# single84.net
KiCad netlist of a schematic drawn in EAGLE
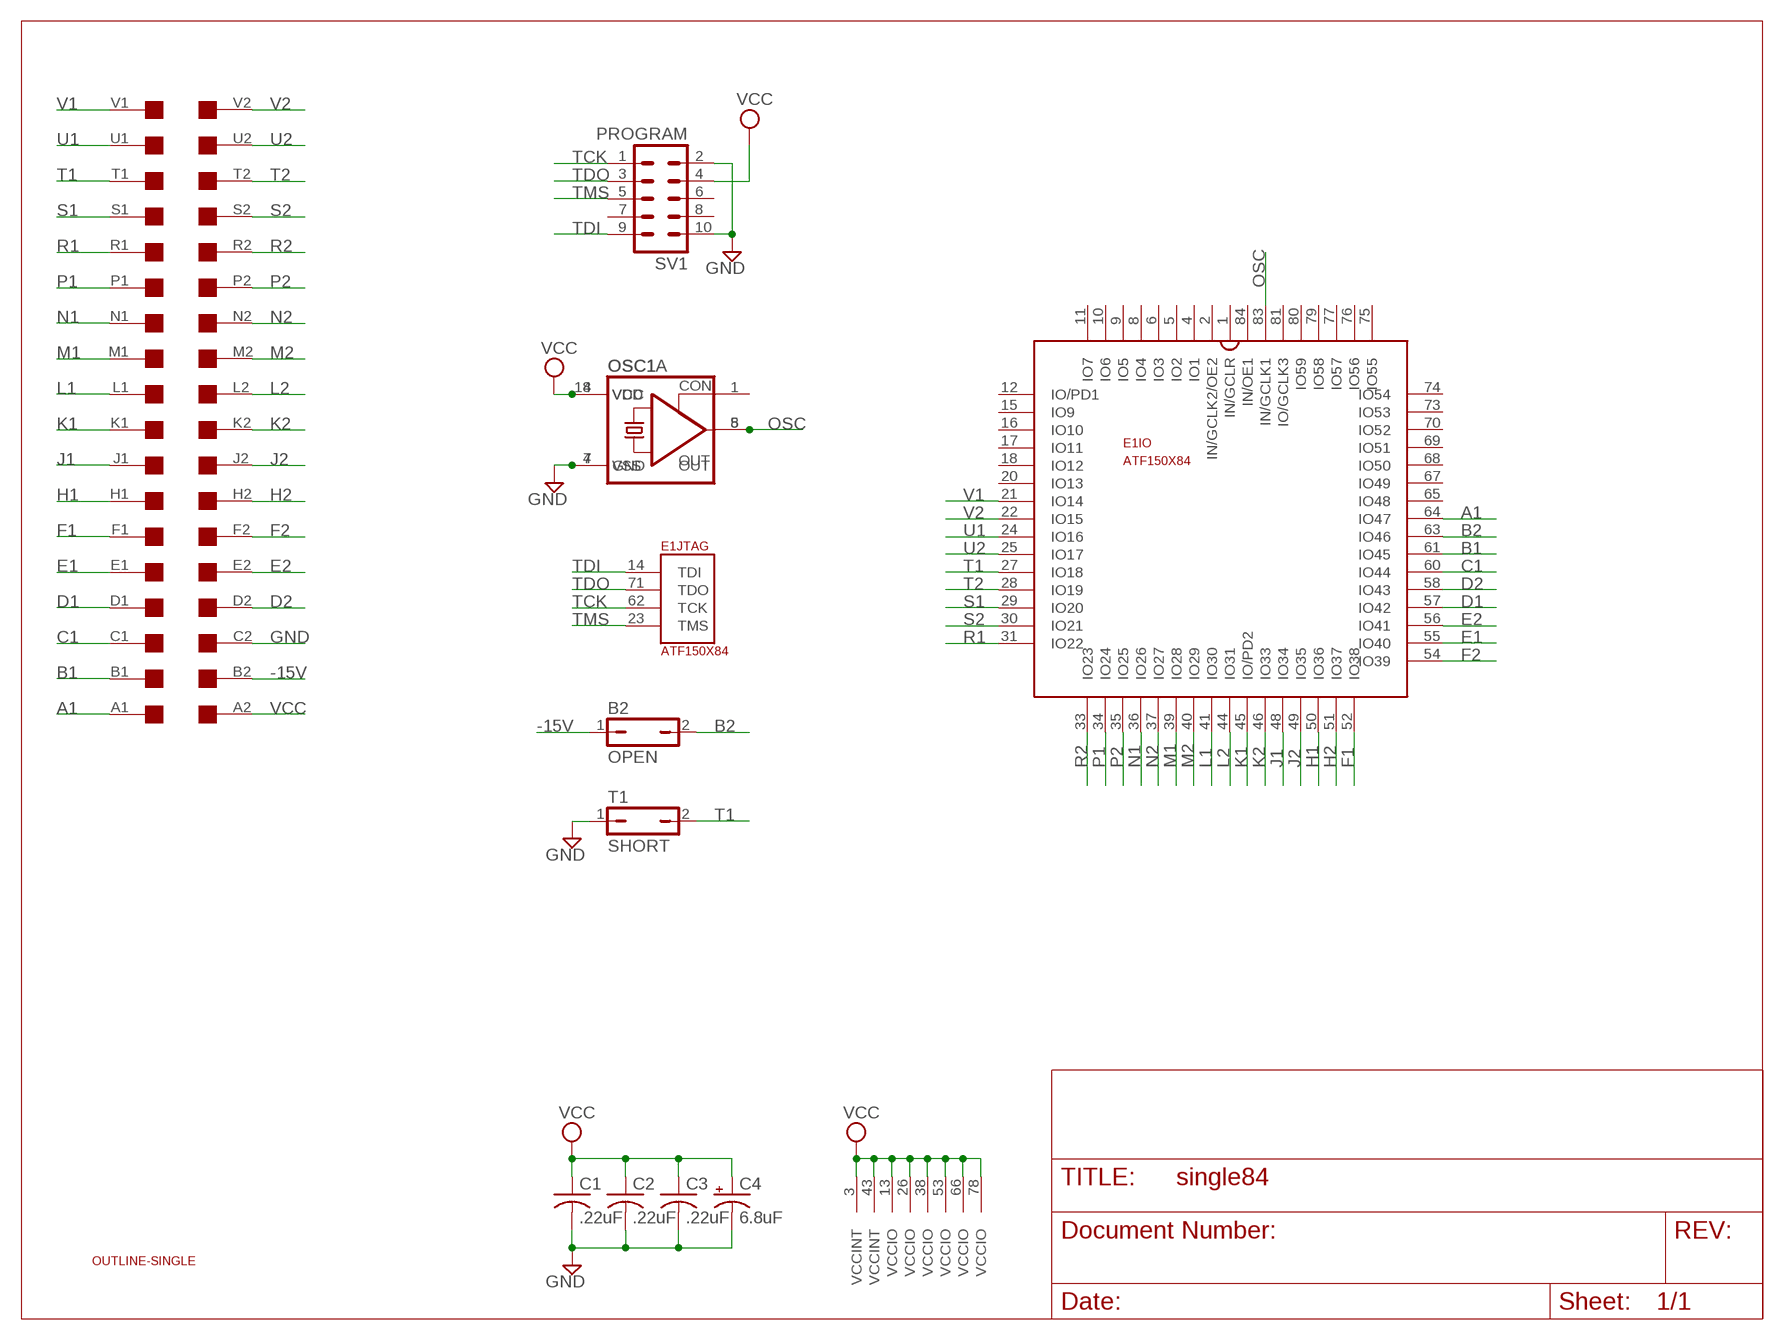
[diagram p0: schematic, sheet 1]

(export (version "E")
  (design (tool "Eeschema 10.0.6"))
  (components
    (comp (ref "B2")
      (value "OPEN")
      (footprint "eagle-import:JP1")
      (libsource (lib "eagle-import") (part "JP1Q"))
    )
    (comp (ref "C1")
      (value ".22uF")
      (footprint "eagle-import:C050-025X075")
      (libsource (lib "eagle-import") (part "C-US050-025X075"))
    )
    (comp (ref "C2")
      (value ".22uF")
      (footprint "eagle-import:C050-025X075")
      (libsource (lib "eagle-import") (part "C-US050-025X075"))
    )
    (comp (ref "C3")
      (value ".22uF")
      (footprint "eagle-import:C050-025X075")
      (libsource (lib "eagle-import") (part "C-US050-025X075"))
    )
    (comp (ref "C4")
      (value "6.8uF")
      (footprint "eagle-import:E15-5")
      (libsource (lib "eagle-import") (part "CPOL-USE15-5AXIAL"))
    )
    (comp (ref "E1")
      (value "ATF150X84")
      (footprint "eagle-import:S84")
      (libsource (lib "eagle-import") (part "ATF150X84"))
    )
    (comp (ref "OSC1")
      (value "QG5460")
      (footprint "eagle-import:DIL08S")
      (libsource (lib "eagle-import") (part "QG5460"))
    )
    (comp (ref "OSC1A")
      (value "CRYSTAL_RES-SG51")
      (footprint "eagle-import:SG51")
      (libsource (lib "eagle-import") (part "CRYSTAL_RES-SG51"))
    )
    (comp (ref "SV1")
      (value "PROGRAM")
      (footprint "eagle-import:ML10")
      (libsource (lib "eagle-import") (part "ML10"))
    )
    (comp (ref "T1")
      (value "SHORT")
      (footprint "eagle-import:JP1")
      (libsource (lib "eagle-import") (part "JP1Q"))
    )
    (comp (ref "U$1")
      (value "OUTLINE-SINGLE")
      (footprint "eagle-import:SINGLE")
      (libsource (lib "eagle-import") (part "OUTLINE-SINGLE"))
    )
    (comp (ref "U$2")
      (value "SINGLE")
      (footprint "eagle-import:EDGE-CON2")
      (libsource (lib "eagle-import") (part "SINGLE"))
    )
  )
  (nets
    (net (code "1") (name "/-15V") (class "Default")
      (node (ref "B2") (pin "1") (pinfunction "1_1") (pintype "passive"))
      (node (ref "U$2") (pin "B2") (pinfunction "1_B2") (pintype "bidirectional"))
    )
    (net (code "2") (name "/A1") (class "Default")
      (node (ref "E1") (pin "64") (pinfunction "IO47_64") (pintype "bidirectional"))
      (node (ref "U$2") (pin "A1") (pinfunction "1_A1") (pintype "bidirectional"))
    )
    (net (code "3") (name "/B1") (class "Default")
      (node (ref "E1") (pin "61") (pinfunction "IO45_61") (pintype "bidirectional"))
      (node (ref "U$2") (pin "B1") (pinfunction "1_B1") (pintype "bidirectional"))
    )
    (net (code "4") (name "/B2") (class "Default")
      (node (ref "B2") (pin "2") (pinfunction "2_2") (pintype "passive"))
      (node (ref "E1") (pin "63") (pinfunction "IO46_63") (pintype "bidirectional"))
    )
    (net (code "5") (name "/C1") (class "Default")
      (node (ref "E1") (pin "60") (pinfunction "IO44_60") (pintype "bidirectional"))
      (node (ref "U$2") (pin "C1") (pinfunction "1_C1") (pintype "bidirectional"))
    )
    (net (code "6") (name "/D1") (class "Default")
      (node (ref "E1") (pin "57") (pinfunction "IO42_57") (pintype "bidirectional"))
      (node (ref "U$2") (pin "D1") (pinfunction "1_D1") (pintype "bidirectional"))
    )
    (net (code "7") (name "/D2") (class "Default")
      (node (ref "E1") (pin "58") (pinfunction "IO43_58") (pintype "bidirectional"))
      (node (ref "U$2") (pin "D2") (pinfunction "1_D2") (pintype "bidirectional"))
    )
    (net (code "8") (name "/E1") (class "Default")
      (node (ref "E1") (pin "55") (pinfunction "IO40_55") (pintype "bidirectional"))
      (node (ref "U$2") (pin "E1") (pinfunction "1_E1") (pintype "bidirectional"))
    )
    (net (code "9") (name "/E2") (class "Default")
      (node (ref "E1") (pin "56") (pinfunction "IO41_56") (pintype "bidirectional"))
      (node (ref "U$2") (pin "E2") (pinfunction "1_E2") (pintype "bidirectional"))
    )
    (net (code "10") (name "/F1") (class "Default")
      (node (ref "E1") (pin "52") (pinfunction "IO38_52") (pintype "bidirectional"))
      (node (ref "U$2") (pin "F1") (pinfunction "1_F1") (pintype "bidirectional"))
    )
    (net (code "11") (name "/F2") (class "Default")
      (node (ref "E1") (pin "54") (pinfunction "IO39_54") (pintype "bidirectional"))
      (node (ref "U$2") (pin "F2") (pinfunction "1_F2") (pintype "bidirectional"))
    )
    (net (code "12") (name "/H1") (class "Default")
      (node (ref "E1") (pin "50") (pinfunction "IO36_50") (pintype "bidirectional"))
      (node (ref "U$2") (pin "H1") (pinfunction "1_H1") (pintype "bidirectional"))
    )
    (net (code "13") (name "/H2") (class "Default")
      (node (ref "E1") (pin "51") (pinfunction "IO37_51") (pintype "bidirectional"))
      (node (ref "U$2") (pin "H2") (pinfunction "1_H2") (pintype "bidirectional"))
    )
    (net (code "14") (name "/J1") (class "Default")
      (node (ref "E1") (pin "48") (pinfunction "IO34_48") (pintype "bidirectional"))
      (node (ref "U$2") (pin "J1") (pinfunction "1_J1") (pintype "bidirectional"))
    )
    (net (code "15") (name "/J2") (class "Default")
      (node (ref "E1") (pin "49") (pinfunction "IO35_49") (pintype "bidirectional"))
      (node (ref "U$2") (pin "J2") (pinfunction "1_J2") (pintype "bidirectional"))
    )
    (net (code "16") (name "/K1") (class "Default")
      (node (ref "E1") (pin "45") (pinfunction "IO/PD2_45") (pintype "bidirectional"))
      (node (ref "U$2") (pin "K1") (pinfunction "1_K1") (pintype "bidirectional"))
    )
    (net (code "17") (name "/K2") (class "Default")
      (node (ref "E1") (pin "46") (pinfunction "IO33_46") (pintype "bidirectional"))
      (node (ref "U$2") (pin "K2") (pinfunction "1_K2") (pintype "bidirectional"))
    )
    (net (code "18") (name "/L1") (class "Default")
      (node (ref "E1") (pin "41") (pinfunction "IO30_41") (pintype "bidirectional"))
      (node (ref "U$2") (pin "L1") (pinfunction "1_L1") (pintype "bidirectional"))
    )
    (net (code "19") (name "/L2") (class "Default")
      (node (ref "E1") (pin "44") (pinfunction "IO31_44") (pintype "bidirectional"))
      (node (ref "U$2") (pin "L2") (pinfunction "1_L2") (pintype "bidirectional"))
    )
    (net (code "20") (name "/M1") (class "Default")
      (node (ref "E1") (pin "39") (pinfunction "IO28_39") (pintype "bidirectional"))
      (node (ref "U$2") (pin "M1") (pinfunction "1_M1") (pintype "bidirectional"))
    )
    (net (code "21") (name "/M2") (class "Default")
      (node (ref "E1") (pin "40") (pinfunction "IO29_40") (pintype "bidirectional"))
      (node (ref "U$2") (pin "M2") (pinfunction "1_M2") (pintype "bidirectional"))
    )
    (net (code "22") (name "/N1") (class "Default")
      (node (ref "E1") (pin "36") (pinfunction "IO26_36") (pintype "bidirectional"))
      (node (ref "U$2") (pin "N1") (pinfunction "1_N1") (pintype "bidirectional"))
    )
    (net (code "23") (name "/N2") (class "Default")
      (node (ref "E1") (pin "37") (pinfunction "IO27_37") (pintype "bidirectional"))
      (node (ref "U$2") (pin "N2") (pinfunction "1_N2") (pintype "bidirectional"))
    )
    (net (code "24") (name "/OSC") (class "Default")
      (node (ref "E1") (pin "83") (pinfunction "IN/GCLK1_83") (pintype "input"))
      (node (ref "OSC1") (pin "5") (pinfunction "OUT_5") (pintype "output"))
      (node (ref "OSC1A") (pin "8") (pinfunction "OUT_8") (pintype "output"))
    )
    (net (code "25") (name "/P1") (class "Default")
      (node (ref "E1") (pin "34") (pinfunction "IO24_34") (pintype "bidirectional"))
      (node (ref "U$2") (pin "P1") (pinfunction "1_P1") (pintype "bidirectional"))
    )
    (net (code "26") (name "/P2") (class "Default")
      (node (ref "E1") (pin "35") (pinfunction "IO25_35") (pintype "bidirectional"))
      (node (ref "U$2") (pin "P2") (pinfunction "1_P2") (pintype "bidirectional"))
    )
    (net (code "27") (name "/R1") (class "Default")
      (node (ref "E1") (pin "31") (pinfunction "IO22_31") (pintype "bidirectional"))
      (node (ref "U$2") (pin "R1") (pinfunction "1_R1") (pintype "bidirectional"))
    )
    (net (code "28") (name "/R2") (class "Default")
      (node (ref "E1") (pin "33") (pinfunction "IO23_33") (pintype "bidirectional"))
      (node (ref "U$2") (pin "R2") (pinfunction "1_R2") (pintype "bidirectional"))
    )
    (net (code "29") (name "/S1") (class "Default")
      (node (ref "E1") (pin "29") (pinfunction "IO20_29") (pintype "bidirectional"))
      (node (ref "U$2") (pin "S1") (pinfunction "1_S1") (pintype "bidirectional"))
    )
    (net (code "30") (name "/S2") (class "Default")
      (node (ref "E1") (pin "30") (pinfunction "IO21_30") (pintype "bidirectional"))
      (node (ref "U$2") (pin "S2") (pinfunction "1_S2") (pintype "bidirectional"))
    )
    (net (code "31") (name "/T1") (class "Default")
      (node (ref "E1") (pin "27") (pinfunction "IO18_27") (pintype "bidirectional"))
      (node (ref "T1") (pin "2") (pinfunction "2_2") (pintype "passive"))
      (node (ref "U$2") (pin "T1") (pinfunction "1_T1") (pintype "bidirectional"))
    )
    (net (code "32") (name "/T2") (class "Default")
      (node (ref "E1") (pin "28") (pinfunction "IO19_28") (pintype "bidirectional"))
      (node (ref "U$2") (pin "T2") (pinfunction "1_T2") (pintype "bidirectional"))
    )
    (net (code "33") (name "/TCK") (class "Default")
      (node (ref "E1") (pin "62") (pinfunction "TCK_62") (pintype "bidirectional"))
      (node (ref "SV1") (pin "1") (pinfunction "1_1") (pintype "passive"))
    )
    (net (code "34") (name "/TDI") (class "Default")
      (node (ref "E1") (pin "14") (pinfunction "TDI_14") (pintype "bidirectional"))
      (node (ref "SV1") (pin "9") (pinfunction "9_9") (pintype "passive"))
    )
    (net (code "35") (name "/TDO") (class "Default")
      (node (ref "E1") (pin "71") (pinfunction "TDO_71") (pintype "bidirectional"))
      (node (ref "SV1") (pin "3") (pinfunction "3_3") (pintype "passive"))
    )
    (net (code "36") (name "/TMS") (class "Default")
      (node (ref "E1") (pin "23") (pinfunction "TMS_23") (pintype "bidirectional"))
      (node (ref "SV1") (pin "5") (pinfunction "5_5") (pintype "passive"))
    )
    (net (code "37") (name "/U1") (class "Default")
      (node (ref "E1") (pin "24") (pinfunction "IO16_24") (pintype "bidirectional"))
      (node (ref "U$2") (pin "U1") (pinfunction "1_U1") (pintype "bidirectional"))
    )
    (net (code "38") (name "/U2") (class "Default")
      (node (ref "E1") (pin "25") (pinfunction "IO17_25") (pintype "bidirectional"))
      (node (ref "U$2") (pin "U2") (pinfunction "1_U2") (pintype "bidirectional"))
    )
    (net (code "39") (name "/V1") (class "Default")
      (node (ref "E1") (pin "21") (pinfunction "IO14_21") (pintype "bidirectional"))
      (node (ref "U$2") (pin "V1") (pinfunction "1_V1") (pintype "bidirectional"))
    )
    (net (code "40") (name "/V2") (class "Default")
      (node (ref "E1") (pin "22") (pinfunction "IO15_22") (pintype "bidirectional"))
      (node (ref "U$2") (pin "V2") (pinfunction "1_V2") (pintype "bidirectional"))
    )
    (net (code "41") (name "GND") (class "Default")
      (node (ref "C1") (pin "2") (pinfunction "2_2") (pintype "passive"))
      (node (ref "C2") (pin "2") (pinfunction "2_2") (pintype "passive"))
      (node (ref "C3") (pin "2") (pinfunction "2_2") (pintype "passive"))
      (node (ref "C4") (pin "-") (pinfunction "-_-") (pintype "passive"))
      (node (ref "OSC1") (pin "4") (pinfunction "GND_4") (pintype "power_in"))
      (node (ref "OSC1A") (pin "7") (pinfunction "VSS_7") (pintype "power_in"))
      (node (ref "SV1") (pin "10") (pinfunction "10_10") (pintype "passive"))
      (node (ref "SV1") (pin "2") (pinfunction "2_2") (pintype "passive"))
      (node (ref "T1") (pin "1") (pinfunction "1_1") (pintype "passive"))
      (node (ref "U$2") (pin "C2") (pinfunction "1_C2") (pintype "bidirectional"))
    )
    (net (code "42") (name "VCC") (class "Default")
      (node (ref "C1") (pin "1") (pinfunction "1_1") (pintype "passive"))
      (node (ref "C2") (pin "1") (pinfunction "1_1") (pintype "passive"))
      (node (ref "C3") (pin "1") (pinfunction "1_1") (pintype "passive"))
      (node (ref "C4") (pin "+") (pinfunction "+_+") (pintype "passive"))
      (node (ref "E1") (pin "13") (pinfunction "VCCIO_13") (pintype "power_in"))
      (node (ref "E1") (pin "26") (pinfunction "VCCIO_26") (pintype "power_in"))
      (node (ref "E1") (pin "3") (pinfunction "VCCINT_3") (pintype "power_in"))
      (node (ref "E1") (pin "38") (pinfunction "VCCIO_38") (pintype "power_in"))
      (node (ref "E1") (pin "43") (pinfunction "VCCINT_43") (pintype "power_in"))
      (node (ref "E1") (pin "53") (pinfunction "VCCIO_53") (pintype "power_in"))
      (node (ref "E1") (pin "66") (pinfunction "VCCIO_66") (pintype "power_in"))
      (node (ref "E1") (pin "78") (pinfunction "VCCIO_78") (pintype "power_in"))
      (node (ref "OSC1") (pin "8") (pinfunction "VCC_8") (pintype "power_in"))
      (node (ref "OSC1A") (pin "14") (pinfunction "VDD_14") (pintype "power_in"))
      (node (ref "SV1") (pin "4") (pinfunction "4_4") (pintype "passive"))
      (node (ref "U$2") (pin "A2") (pinfunction "1_A2") (pintype "bidirectional"))
    )
    (net (code "43") (name "unconnected-(E1Q-IN{slash}GCLK2{slash}OE2-Pad2)") (class "Default")
      (node (ref "E1") (pin "2") (pinfunction "IN/GCLK2/OE2_2") (pintype "input"))
    )
    (net (code "44") (name "unconnected-(E1Q-IN{slash}GCLR-Pad1)") (class "Default")
      (node (ref "E1") (pin "1") (pinfunction "IN/GCLR_1") (pintype "input"))
    )
    (net (code "45") (name "unconnected-(E1Q-IN{slash}OE1-Pad84)") (class "Default")
      (node (ref "E1") (pin "84") (pinfunction "IN/OE1_84") (pintype "input"))
    )
    (net (code "46") (name "unconnected-(E1Q-IO1-Pad4)") (class "Default")
      (node (ref "E1") (pin "4") (pinfunction "IO1_4") (pintype "bidirectional"))
    )
    (net (code "47") (name "unconnected-(E1Q-IO2-Pad5)") (class "Default")
      (node (ref "E1") (pin "5") (pinfunction "IO2_5") (pintype "bidirectional"))
    )
    (net (code "48") (name "unconnected-(E1Q-IO3-Pad6)") (class "Default")
      (node (ref "E1") (pin "6") (pinfunction "IO3_6") (pintype "bidirectional"))
    )
    (net (code "49") (name "unconnected-(E1Q-IO4-Pad8)") (class "Default")
      (node (ref "E1") (pin "8") (pinfunction "IO4_8") (pintype "bidirectional"))
    )
    (net (code "50") (name "unconnected-(E1Q-IO5-Pad9)") (class "Default")
      (node (ref "E1") (pin "9") (pinfunction "IO5_9") (pintype "bidirectional"))
    )
    (net (code "51") (name "unconnected-(E1Q-IO6-Pad10)") (class "Default")
      (node (ref "E1") (pin "10") (pinfunction "IO6_10") (pintype "bidirectional"))
    )
    (net (code "52") (name "unconnected-(E1Q-IO7-Pad11)") (class "Default")
      (node (ref "E1") (pin "11") (pinfunction "IO7_11") (pintype "bidirectional"))
    )
    (net (code "53") (name "unconnected-(E1Q-IO9-Pad15)") (class "Default")
      (node (ref "E1") (pin "15") (pinfunction "IO9_15") (pintype "bidirectional"))
    )
    (net (code "54") (name "unconnected-(E1Q-IO10-Pad16)") (class "Default")
      (node (ref "E1") (pin "16") (pinfunction "IO10_16") (pintype "bidirectional"))
    )
    (net (code "55") (name "unconnected-(E1Q-IO11-Pad17)") (class "Default")
      (node (ref "E1") (pin "17") (pinfunction "IO11_17") (pintype "bidirectional"))
    )
    (net (code "56") (name "unconnected-(E1Q-IO12-Pad18)") (class "Default")
      (node (ref "E1") (pin "18") (pinfunction "IO12_18") (pintype "bidirectional"))
    )
    (net (code "57") (name "unconnected-(E1Q-IO13-Pad20)") (class "Default")
      (node (ref "E1") (pin "20") (pinfunction "IO13_20") (pintype "bidirectional"))
    )
    (net (code "58") (name "unconnected-(E1Q-IO48-Pad65)") (class "Default")
      (node (ref "E1") (pin "65") (pinfunction "IO48_65") (pintype "bidirectional"))
    )
    (net (code "59") (name "unconnected-(E1Q-IO49-Pad67)") (class "Default")
      (node (ref "E1") (pin "67") (pinfunction "IO49_67") (pintype "bidirectional"))
    )
    (net (code "60") (name "unconnected-(E1Q-IO50-Pad68)") (class "Default")
      (node (ref "E1") (pin "68") (pinfunction "IO50_68") (pintype "bidirectional"))
    )
    (net (code "61") (name "unconnected-(E1Q-IO51-Pad69)") (class "Default")
      (node (ref "E1") (pin "69") (pinfunction "IO51_69") (pintype "bidirectional"))
    )
    (net (code "62") (name "unconnected-(E1Q-IO52-Pad70)") (class "Default")
      (node (ref "E1") (pin "70") (pinfunction "IO52_70") (pintype "bidirectional"))
    )
    (net (code "63") (name "unconnected-(E1Q-IO53-Pad73)") (class "Default")
      (node (ref "E1") (pin "73") (pinfunction "IO53_73") (pintype "bidirectional"))
    )
    (net (code "64") (name "unconnected-(E1Q-IO54-Pad74)") (class "Default")
      (node (ref "E1") (pin "74") (pinfunction "IO54_74") (pintype "bidirectional"))
    )
    (net (code "65") (name "unconnected-(E1Q-IO55-Pad75)") (class "Default")
      (node (ref "E1") (pin "75") (pinfunction "IO55_75") (pintype "bidirectional"))
    )
    (net (code "66") (name "unconnected-(E1Q-IO56-Pad76)") (class "Default")
      (node (ref "E1") (pin "76") (pinfunction "IO56_76") (pintype "bidirectional"))
    )
    (net (code "67") (name "unconnected-(E1Q-IO57-Pad77)") (class "Default")
      (node (ref "E1") (pin "77") (pinfunction "IO57_77") (pintype "bidirectional"))
    )
    (net (code "68") (name "unconnected-(E1Q-IO58-Pad79)") (class "Default")
      (node (ref "E1") (pin "79") (pinfunction "IO58_79") (pintype "bidirectional"))
    )
    (net (code "69") (name "unconnected-(E1Q-IO59-Pad80)") (class "Default")
      (node (ref "E1") (pin "80") (pinfunction "IO59_80") (pintype "bidirectional"))
    )
    (net (code "70") (name "unconnected-(E1Q-IO{slash}GCLK3-Pad81)") (class "Default")
      (node (ref "E1") (pin "81") (pinfunction "IO/GCLK3_81") (pintype "bidirectional"))
    )
    (net (code "71") (name "unconnected-(E1Q-IO{slash}PD1-Pad12)") (class "Default")
      (node (ref "E1") (pin "12") (pinfunction "IO/PD1_12") (pintype "bidirectional"))
    )
    (net (code "72") (name "unconnected-(OSC1A-CON-Pad1)") (class "Default")
      (node (ref "OSC1A") (pin "1") (pinfunction "CON_1") (pintype "input"))
    )
    (net (code "73") (name "unconnected-(SV1-Pad6)") (class "Default")
      (node (ref "SV1") (pin "6") (pinfunction "6_6") (pintype "passive"))
    )
    (net (code "74") (name "unconnected-(SV1-Pad7)") (class "Default")
      (node (ref "SV1") (pin "7") (pinfunction "7_7") (pintype "passive"))
    )
    (net (code "75") (name "unconnected-(SV1-Pad8)") (class "Default")
      (node (ref "SV1") (pin "8") (pinfunction "8_8") (pintype "passive"))
    )
  )
)
